# SEPIC-MT3608_2025-10-18.net
KiCad netlist of a schematic drawn in Altium Designer
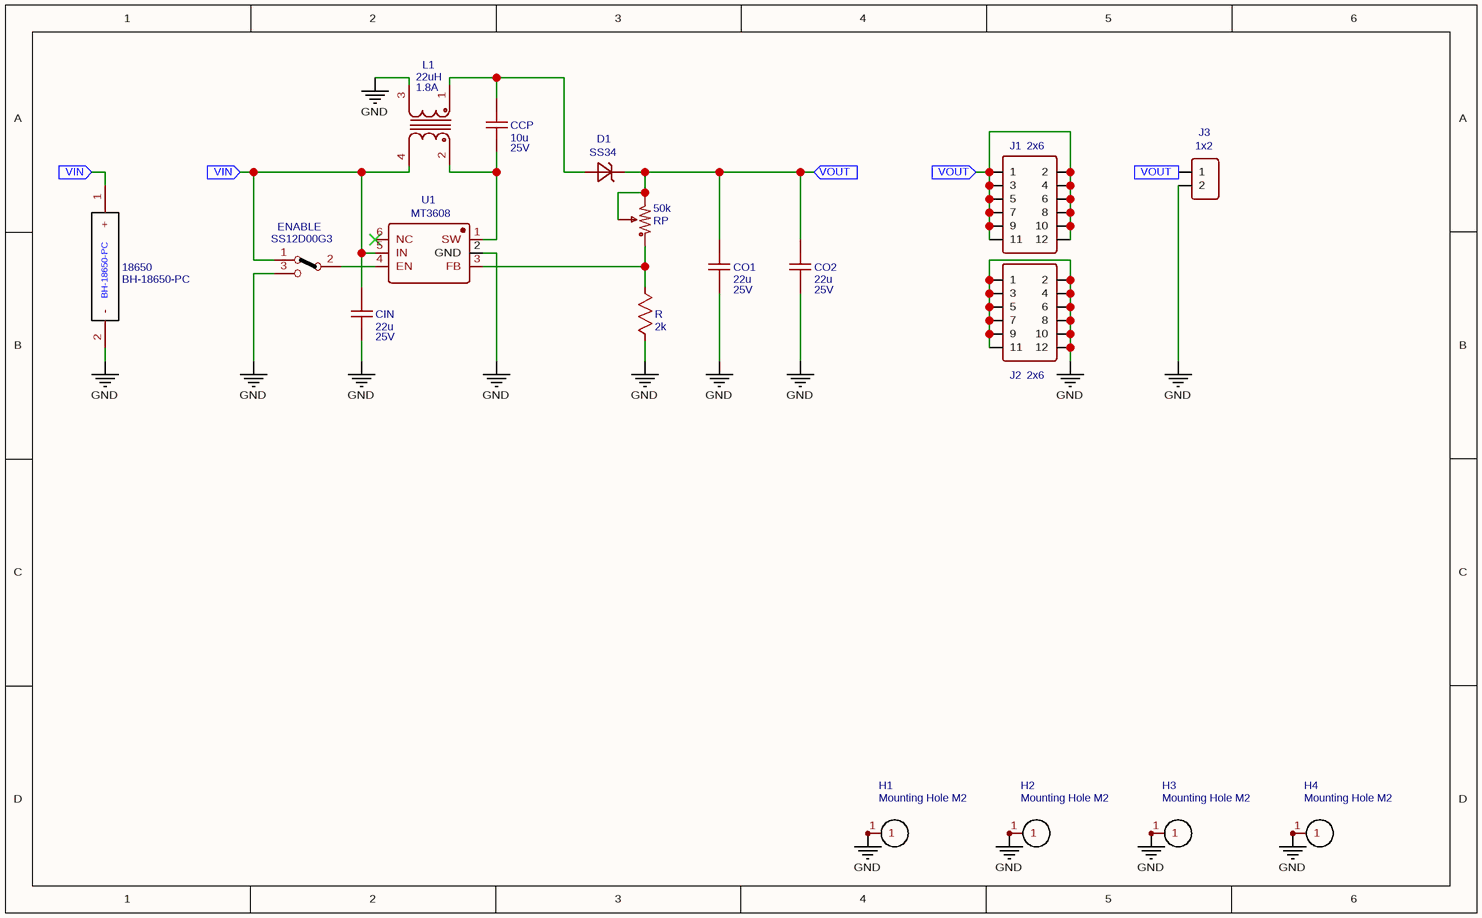
[diagram p0: SEPIC-MT3608_2025-10-18.schdoc]

(export (version "E")
  (design (tool "Eeschema 10.0.6"))
  (components
    (comp (ref "18650")
      (value "BH-18650-PC")
      (fields (field (name "CONTRIBUTOR") "anton_8359"))
      (libsource (lib "altium-import") (part "root_0_BH-18650-PC_"))
    )
    (comp (ref "CCP")
      (value "10u")
      (fields (field (name "CONTRIBUTOR") "LCEDA_Lib"))
      (libsource (lib "altium-import") (part "root_1_10u_"))
    )
    (comp (ref "CIN")
      (value "22u")
      (fields (field (name "MANUFACTURER") "SAMSUNG") (field (name "MANUFACTURER PART") "CL32A226KAJNNNE"))
      (libsource (lib "altium-import") (part "root_3_22u_"))
    )
    (comp (ref "CO1")
      (value "22u")
      (fields (field (name "MANUFACTURER") "SAMSUNG") (field (name "MANUFACTURER PART") "CL32A226KAJNNNE"))
      (libsource (lib "altium-import") (part "root_3_22u_"))
    )
    (comp (ref "CO2")
      (value "22u")
      (fields (field (name "MANUFACTURER") "SAMSUNG") (field (name "MANUFACTURER PART") "CL32A226KAJNNNE"))
      (libsource (lib "altium-import") (part "root_3_22u_"))
    )
    (comp (ref "D1")
      (value "SS34")
      (fields
        (field (name "MANUFACTURER") "BLUE ROCKET(蓝箭)")
        (field (name "MANUFACTURER PART") "SMBJ100A")
        (field (name "CONTRIBUTOR") "LCSC")
      )
      (libsource (lib "altium-import") (part "root_2_SS34_"))
    )
    (comp (ref "ENABLE")
      (value "SS12D00G3")
      (fields (field (name "MANUFACTURER PART") "Switch SPDT") (field (name "CONTRIBUTOR") "hofteboy"))
      (libsource (lib "altium-import") (part "root_0_SS12D00G3_"))
    )
    (comp (ref "H1")
      (value "Mounting Hole M2")
      (fields (field (name "CONTRIBUTOR") "mieliepit911"))
      (libsource (lib "altium-import") (part "root_0_Mounting Hole M2_"))
    )
    (comp (ref "H2")
      (value "Mounting Hole M2")
      (fields (field (name "CONTRIBUTOR") "mieliepit911"))
      (libsource (lib "altium-import") (part "root_0_Mounting Hole M2_"))
    )
    (comp (ref "H3")
      (value "Mounting Hole M2")
      (fields (field (name "CONTRIBUTOR") "mieliepit911"))
      (libsource (lib "altium-import") (part "root_0_Mounting Hole M2_"))
    )
    (comp (ref "H4")
      (value "Mounting Hole M2")
      (fields (field (name "CONTRIBUTOR") "mieliepit911"))
      (libsource (lib "altium-import") (part "root_0_Mounting Hole M2_"))
    )
    (comp (ref "J1")
      (value "2x6")
      (fields (field (name "CONTRIBUTOR") "LCEDA_Lib"))
      (libsource (lib "altium-import") (part "root_0_2x6_"))
    )
    (comp (ref "J2")
      (value "2x6")
      (fields (field (name "CONTRIBUTOR") "LCEDA_Lib"))
      (libsource (lib "altium-import") (part "root_0_2x6_"))
    )
    (comp (ref "J3")
      (value "1x2")
      (fields (field (name "CONTRIBUTOR") "LCEDA_Lib"))
      (libsource (lib "altium-import") (part "root_0_1x2_"))
    )
    (comp (ref "L1")
      (value "22uH")
      (fields (field (name "MANUFACTURER PART") "DRQ74-220-R") (field (name "CONTRIBUTOR") "LCSC"))
      (libsource (lib "altium-import") (part "root_3_22uH_"))
    )
    (comp (ref "R")
      (value "2k")
      (fields (field (name "CONTRIBUTOR") "LCEDA_Lib"))
      (libsource (lib "altium-import") (part "root_1_2k_"))
    )
    (comp (ref "RP")
      (value "50k")
      (fields (field (name "CONTRIBUTOR") "LCEDA_Lib"))
      (libsource (lib "altium-import") (part "root_1_50k_"))
    )
    (comp (ref "U1")
      (value "MT3608")
      (fields (field (name "MANUFACTURER") "AEROSEMI"))
      (libsource (lib "altium-import") (part "root_0_MT3608_"))
    )
  )
  (nets
    (net (code "1") (name "/VIN") (class "Default")
      (node (ref "18650") (pin "1") (pinfunction "+_1") (pintype "passive"))
      (node (ref "CIN") (pin "1") (pinfunction "1_1") (pintype "passive"))
      (node (ref "ENABLE") (pin "1") (pinfunction "C_1") (pintype "passive"))
      (node (ref "L1") (pin "4") (pinfunction "4_4") (pintype "passive"))
      (node (ref "U1") (pin "5") (pinfunction "IN_5") (pintype "passive"))
    )
    (net (code "2") (name "/VOUT") (class "Default")
      (node (ref "CO1") (pin "1") (pinfunction "1_1") (pintype "passive"))
      (node (ref "CO2") (pin "1") (pinfunction "1_1") (pintype "passive"))
      (node (ref "D1") (pin "1") (pinfunction "1_1") (pintype "passive"))
      (node (ref "J1") (pin "1") (pinfunction "1_1") (pintype "passive"))
      (node (ref "J1") (pin "10") (pinfunction "10_10") (pintype "passive"))
      (node (ref "J1") (pin "11") (pinfunction "11_11") (pintype "passive"))
      (node (ref "J1") (pin "12") (pinfunction "12_12") (pintype "passive"))
      (node (ref "J1") (pin "2") (pinfunction "2_2") (pintype "passive"))
      (node (ref "J1") (pin "3") (pinfunction "3_3") (pintype "passive"))
      (node (ref "J1") (pin "4") (pinfunction "4_4") (pintype "passive"))
      (node (ref "J1") (pin "5") (pinfunction "5_5") (pintype "passive"))
      (node (ref "J1") (pin "6") (pinfunction "6_6") (pintype "passive"))
      (node (ref "J1") (pin "7") (pinfunction "7_7") (pintype "passive"))
      (node (ref "J1") (pin "8") (pinfunction "8_8") (pintype "passive"))
      (node (ref "J1") (pin "9") (pinfunction "9_9") (pintype "passive"))
      (node (ref "J3") (pin "1") (pinfunction "1_1") (pintype "passive"))
      (node (ref "RP") (pin "2") (pinfunction "2_2") (pintype "passive"))
      (node (ref "RP") (pin "3") (pinfunction "3_3") (pintype "passive"))
    )
    (net (code "3") (name "GND") (class "Default")
      (node (ref "18650") (pin "2") (pinfunction "-_2") (pintype "passive"))
      (node (ref "CIN") (pin "2") (pinfunction "2_2") (pintype "passive"))
      (node (ref "CO1") (pin "2") (pinfunction "2_2") (pintype "passive"))
      (node (ref "CO2") (pin "2") (pinfunction "2_2") (pintype "passive"))
      (node (ref "ENABLE") (pin "3") (pinfunction "NO_3") (pintype "passive"))
      (node (ref "H1") (pin "1") (pinfunction "1_1") (pintype "passive"))
      (node (ref "H2") (pin "1") (pinfunction "1_1") (pintype "passive"))
      (node (ref "H3") (pin "1") (pinfunction "1_1") (pintype "passive"))
      (node (ref "H4") (pin "1") (pinfunction "1_1") (pintype "passive"))
      (node (ref "J2") (pin "1") (pinfunction "1_1") (pintype "passive"))
      (node (ref "J2") (pin "10") (pinfunction "10_10") (pintype "passive"))
      (node (ref "J2") (pin "11") (pinfunction "11_11") (pintype "passive"))
      (node (ref "J2") (pin "12") (pinfunction "12_12") (pintype "passive"))
      (node (ref "J2") (pin "2") (pinfunction "2_2") (pintype "passive"))
      (node (ref "J2") (pin "3") (pinfunction "3_3") (pintype "passive"))
      (node (ref "J2") (pin "4") (pinfunction "4_4") (pintype "passive"))
      (node (ref "J2") (pin "5") (pinfunction "5_5") (pintype "passive"))
      (node (ref "J2") (pin "6") (pinfunction "6_6") (pintype "passive"))
      (node (ref "J2") (pin "7") (pinfunction "7_7") (pintype "passive"))
      (node (ref "J2") (pin "8") (pinfunction "8_8") (pintype "passive"))
      (node (ref "J2") (pin "9") (pinfunction "9_9") (pintype "passive"))
      (node (ref "J3") (pin "2") (pinfunction "2_2") (pintype "passive"))
      (node (ref "L1") (pin "3") (pinfunction "3_3") (pintype "passive"))
      (node (ref "R") (pin "1") (pinfunction "1_1") (pintype "passive"))
      (node (ref "U1") (pin "2") (pinfunction "GND_2") (pintype "passive"))
    )
    (net (code "4") (name "Net-(CCP-Pad2)") (class "Default")
      (node (ref "CCP") (pin "2") (pinfunction "2_2") (pintype "passive"))
      (node (ref "D1") (pin "2") (pinfunction "2_2") (pintype "passive"))
      (node (ref "L1") (pin "1") (pinfunction "1_1") (pintype "passive"))
    )
    (net (code "5") (name "Net-(ENABLE-NC)") (class "Default")
      (node (ref "ENABLE") (pin "2") (pinfunction "NC_2") (pintype "passive"))
      (node (ref "U1") (pin "4") (pinfunction "EN_4") (pintype "passive"))
    )
    (net (code "6") (name "Net-(U1-FB)") (class "Default")
      (node (ref "R") (pin "2") (pinfunction "2_2") (pintype "passive"))
      (node (ref "RP") (pin "1") (pinfunction "1_1") (pintype "passive"))
      (node (ref "U1") (pin "3") (pinfunction "FB_3") (pintype "passive"))
    )
    (net (code "7") (name "Net-(U1-SW)") (class "Default")
      (node (ref "CCP") (pin "1") (pinfunction "1_1") (pintype "passive"))
      (node (ref "L1") (pin "2") (pinfunction "2_2") (pintype "passive"))
      (node (ref "U1") (pin "1") (pinfunction "SW_1") (pintype "passive"))
    )
    (net (code "8") (name "unconnected-(U1-NC-Pad6)") (class "Default")
      (node (ref "U1") (pin "6") (pinfunction "NC_6") (pintype "passive+no_connect"))
    )
  )
)
